# Power.net
KiCad netlist of a schematic drawn in Altium Designer
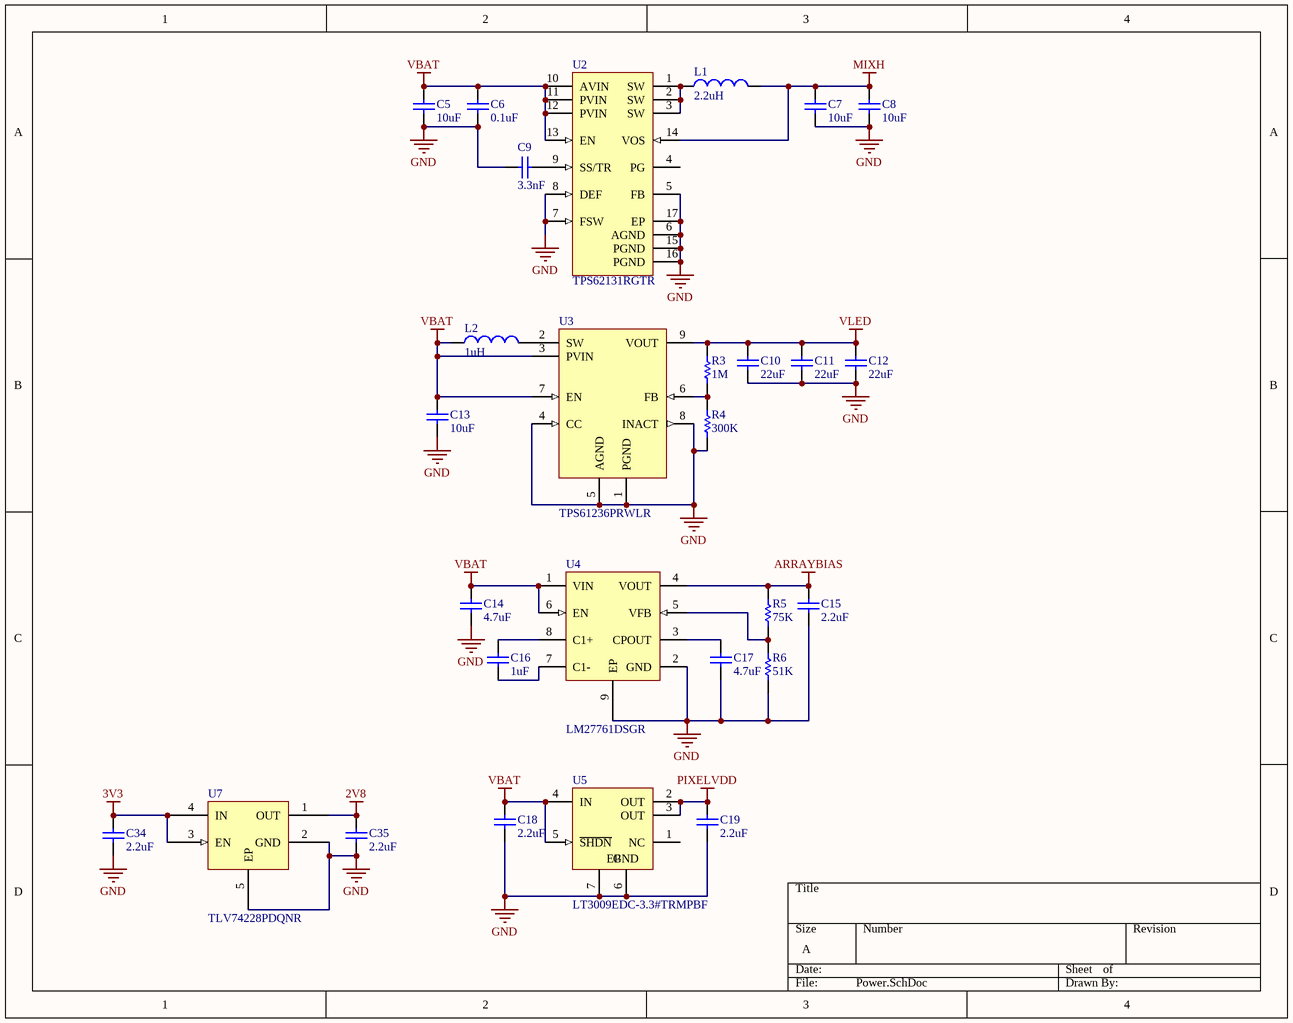
[diagram p0: Power.SchDoc]

(export (version "E")
  (design (tool "Eeschema 10.0.6"))
  (components
    (comp (ref "C5")
      (value "10uF")
      (footprint "C0402[1005X55]")
      (description "10uF 6.3V 20% 0402 (1005 Metric)")
      (fields (field (name "PARTNUMBER") "GRM155R60J106ME44D") (field (name "MANUFACTURER") "Murata"))
      (libsource (lib "Capacitors") (part "CAP_10uF_6.3V_0402_20%"))
    )
    (comp (ref "C6")
      (value "0.1uF")
      (footprint "C0201[0603X30]")
      (description "0.1uF 6.3V 10% 0201 (0603 Metric)")
      (fields (field (name "PARTNUMBER") "GRT033R60J104KE01D") (field (name "MANUFACTURER") "Murata"))
      (libsource (lib "Capacitors") (part "CAP_0.1uF_6.3V_0201_10%"))
    )
    (comp (ref "C7")
      (value "10uF")
      (footprint "C0402[1005X55]")
      (description "10uF 6.3V 20% 0402 (1005 Metric)")
      (fields (field (name "PARTNUMBER") "GRM155R60J106ME44D") (field (name "MANUFACTURER") "Murata"))
      (libsource (lib "Capacitors") (part "CAP_10uF_6.3V_0402_20%"))
    )
    (comp (ref "C8")
      (value "10uF")
      (footprint "C0402[1005X55]")
      (description "10uF 6.3V 20% 0402 (1005 Metric)")
      (fields (field (name "PARTNUMBER") "GRM155R60J106ME44D") (field (name "MANUFACTURER") "Murata"))
      (libsource (lib "Capacitors") (part "CAP_10uF_6.3V_0402_20%"))
    )
    (comp (ref "C9")
      (value "3.3nF")
      (footprint "C0201[0603X30]")
      (description "3.3nF 6.3V 10% 0201 (0603 Metric)")
      (fields (field (name "PARTNUMBER") "GRM033R70J332KA01D") (field (name "MANUFACTURER") "Murata"))
      (libsource (lib "Capacitors") (part "CAP_3,3nF_6.3V_0201_10%"))
    )
    (comp (ref "C10")
      (value "22uF")
      (footprint "C0603[1608X92]")
      (description "22uF 6.3V 10% 0603 (1608 Metric)")
      (fields (field (name "PARTNUMBER") "GRT188R60J226ME13D") (field (name "MANUFACTURER") "Murata"))
      (libsource (lib "Capacitors") (part "CAP_22uF_6.3V_0603_10%"))
    )
    (comp (ref "C11")
      (value "22uF")
      (footprint "C0603[1608X92]")
      (description "22uF 6.3V 10% 0603 (1608 Metric)")
      (fields (field (name "PARTNUMBER") "GRT188R60J226ME13D") (field (name "MANUFACTURER") "Murata"))
      (libsource (lib "Capacitors") (part "CAP_22uF_6.3V_0603_10%"))
    )
    (comp (ref "C12")
      (value "22uF")
      (footprint "C0603[1608X92]")
      (description "22uF 6.3V 10% 0603 (1608 Metric)")
      (fields (field (name "PARTNUMBER") "GRT188R60J226ME13D") (field (name "MANUFACTURER") "Murata"))
      (libsource (lib "Capacitors") (part "CAP_22uF_6.3V_0603_10%"))
    )
    (comp (ref "C13")
      (value "10uF")
      (footprint "C0402[1005X55]")
      (description "10uF 6.3V 20% 0402 (1005 Metric)")
      (fields (field (name "PARTNUMBER") "GRM155R60J106ME44D") (field (name "MANUFACTURER") "Murata"))
      (libsource (lib "Capacitors") (part "CAP_10uF_6.3V_0402_20%"))
    )
    (comp (ref "C14")
      (value "4.7uF")
      (footprint "C0402[1005X55]")
      (description "4.7uF 6.3V 20% 0402 (1005 Metric)")
      (fields (field (name "PARTNUMBER") "GRM155R60J475ME47D") (field (name "MANUFACTURER") "Murata"))
      (libsource (lib "Capacitors") (part "CAP_4.7uF_6.3V_0402_20%"))
    )
    (comp (ref "C15")
      (value "2.2uF")
      (footprint "C0402[1005X55]")
      (description "2.2uF 6.3V 20% 0402 (1005 Metric)")
      (fields (field (name "PARTNUMBER") "GRM155R60J225ME15D") (field (name "MANUFACTURER") "Murata"))
      (libsource (lib "Capacitors") (part "CAP_2.2uF_6.3V_0402_20%"))
    )
    (comp (ref "C16")
      (value "1uF")
      (footprint "C0402[1005X55]")
      (description "1uF 6.3V 10% 0402 (1005 Metric)")
      (fields (field (name "PARTNUMBER") "GRM155R70J105KA12D") (field (name "MANUFACTURER") "Murata"))
      (libsource (lib "Capacitors") (part "CAP_1uF_6.3V_0402_10%"))
    )
    (comp (ref "C17")
      (value "4.7uF")
      (footprint "C0402[1005X55]")
      (description "4.7uF 6.3V 20% 0402 (1005 Metric)")
      (fields (field (name "PARTNUMBER") "GRM155R60J475ME47D") (field (name "MANUFACTURER") "Murata"))
      (libsource (lib "Capacitors") (part "CAP_4.7uF_6.3V_0402_20%"))
    )
    (comp (ref "C18")
      (value "2.2uF")
      (footprint "C0402[1005X55]")
      (description "2.2uF 6.3V 20% 0402 (1005 Metric)")
      (fields (field (name "PARTNUMBER") "GRM155R60J225ME15D") (field (name "MANUFACTURER") "Murata"))
      (libsource (lib "Capacitors") (part "CAP_2.2uF_6.3V_0402_20%"))
    )
    (comp (ref "C19")
      (value "2.2uF")
      (footprint "C0402[1005X55]")
      (description "2.2uF 6.3V 20% 0402 (1005 Metric)")
      (fields (field (name "PARTNUMBER") "GRM155R60J225ME15D") (field (name "MANUFACTURER") "Murata"))
      (libsource (lib "Capacitors") (part "CAP_2.2uF_6.3V_0402_20%"))
    )
    (comp (ref "C34")
      (value "2.2uF")
      (footprint "C0402[1005X55]")
      (description "2.2uF 6.3V 20% 0402 (1005 Metric)")
      (fields (field (name "PARTNUMBER") "GRM155R60J225ME15D") (field (name "MANUFACTURER") "Murata"))
      (libsource (lib "Capacitors") (part "CAP_2.2uF_6.3V_0402_20%"))
    )
    (comp (ref "C35")
      (value "2.2uF")
      (footprint "C0402[1005X55]")
      (description "2.2uF 6.3V 20% 0402 (1005 Metric)")
      (fields (field (name "PARTNUMBER") "GRM155R60J225ME15D") (field (name "MANUFACTURER") "Murata"))
      (libsource (lib "Capacitors") (part "CAP_2.2uF_6.3V_0402_20%"))
    )
    (comp (ref "L1")
      (value "2.2uH")
      (footprint "IND1008")
      (description "2.2uH 20% 3.3A 1008")
      (fields (field (name "PARTNUMBER") "DFE252012F-2R2M=P2") (field (name "MANUFACTURER") "Murata"))
      (libsource (lib "Inductors") (part "IND_2.2uH_3.3A_1008_20%"))
    )
    (comp (ref "L2")
      (value "1uH")
      (footprint "IND1008")
      (description "1uH 20% 4.7A 1008")
      (fields (field (name "PARTNUMBER") "DFE252012F-2R2M=P2") (field (name "MANUFACTURER") "Murata"))
      (libsource (lib "Inductors") (part "IND_1uH_4.7A_1008_20%"))
    )
    (comp (ref "R3")
      (value "1M")
      (footprint "R0402[1005]")
      (description "1M 0.063W 1% 0402 (1005 Metric)")
      (fields (field (name "MANUFACTURER") "KOA Speer") (field (name "PARTNUMBER") "RK73H1ETTP1004F"))
      (libsource (lib "Resistors") (part "RES_1M_0402_1%"))
    )
    (comp (ref "R4")
      (value "300K")
      (footprint "R0402[1005]")
      (description "300K 0.063W 1% 0402 (1005 Metric)")
      (fields (field (name "MANUFACTURER") "KOA Speer") (field (name "PARTNUMBER") "RK73H1ETTP3003F"))
      (libsource (lib "Resistors") (part "RES_300K_0402_1%"))
    )
    (comp (ref "R5")
      (value "75K")
      (footprint "R0402[1005]")
      (description "75K 0.063W 1% 0402 (1005 Metric)")
      (fields (field (name "MANUFACTURER") "KOA Speer") (field (name "PARTNUMBER") "RK73H1ETTP7502F"))
      (libsource (lib "Resistors") (part "RES_75K_0402_1%"))
    )
    (comp (ref "R6")
      (value "51K")
      (footprint "R0402[1005]")
      (description "51K 0.063W 1% 0402 (1005 Metric)")
      (fields (field (name "MANUFACTURER") "KOA Speer") (field (name "PARTNUMBER") "RK73H1ETTP5102F"))
      (libsource (lib "Resistors") (part "RES_51K_0402_1%"))
    )
    (comp (ref "U2")
      (value "TPS62131RGTR")
      (footprint "RGT0016C_V")
      (fields (field (name "MANUFACTURER") "Texas Instruments"))
      (libsource (lib "Altium Content Vault") (part "TI-TPS62131RGT16-1700X1700TP"))
    )
    (comp (ref "U3")
      (value "TPS61236PRWLR")
      (footprint "VQFN-9")
      (fields (field (name "MANUFACTURER") "Texas Instruments"))
      (libsource (lib "ICs") (part "TPS61236PRWLR"))
    )
    (comp (ref "U4")
      (value "LM27761DSGR")
      (footprint "WSON-8")
      (description "Switching Voltage Regulators Switch Cap Boost")
      (fields (field (name "MANUFACTURER") "Texas Instruments"))
      (libsource (lib "ICs") (part "LM27761DSGR"))
    )
    (comp (ref "U5")
      (value "LT3009EDC-3.3#TRMPBF")
      (footprint "LT-DC6-6_V")
      (fields (field (name "MANUFACTURER") "Linear Technology"))
      (libsource (lib "Altium Content Vault") (part "LT-LT3009-DC6-6"))
    )
    (comp (ref "U7")
      (value "TLV74228PDQNR")
      (footprint "X2SON-4")
      (fields (field (name "MANUFACTURER") "Texas Instruments") (field (name "PARTNUMBER") "TLV74218PDQNR"))
      (libsource (lib "ICs") (part "TLV74228PDQNR"))
    )
  )
  (nets
    (net (code "1") (name "2V8") (class "Default")
      (node (ref "C35") (pin "2") (pinfunction "2_2") (pintype "passive"))
      (node (ref "U7") (pin "1") (pinfunction "OUT_1") (pintype "power_in"))
    )
    (net (code "2") (name "3V3") (class "Default")
      (node (ref "C34") (pin "2") (pinfunction "2_2") (pintype "passive"))
      (node (ref "U7") (pin "3") (pinfunction "EN_3") (pintype "input"))
      (node (ref "U7") (pin "4") (pinfunction "IN_4") (pintype "power_in"))
    )
    (net (code "3") (name "ARRAYBIAS") (class "Default")
      (node (ref "C15") (pin "2") (pinfunction "2_2") (pintype "passive"))
      (node (ref "R5") (pin "2") (pinfunction "2_2") (pintype "passive"))
      (node (ref "U4") (pin "4") (pinfunction "VOUT_4") (pintype "power_in"))
    )
    (net (code "4") (name "GND") (class "Default")
      (node (ref "C10") (pin "1") (pinfunction "1_1") (pintype "passive"))
      (node (ref "C11") (pin "1") (pinfunction "1_1") (pintype "passive"))
      (node (ref "C12") (pin "1") (pinfunction "1_1") (pintype "passive"))
      (node (ref "C13") (pin "1") (pinfunction "1_1") (pintype "passive"))
      (node (ref "C14") (pin "1") (pinfunction "1_1") (pintype "passive"))
      (node (ref "C15") (pin "1") (pinfunction "1_1") (pintype "passive"))
      (node (ref "C17") (pin "1") (pinfunction "1_1") (pintype "passive"))
      (node (ref "C18") (pin "1") (pinfunction "1_1") (pintype "passive"))
      (node (ref "C19") (pin "1") (pinfunction "1_1") (pintype "passive"))
      (node (ref "C34") (pin "1") (pinfunction "1_1") (pintype "passive"))
      (node (ref "C35") (pin "1") (pinfunction "1_1") (pintype "passive"))
      (node (ref "C5") (pin "1") (pinfunction "1_1") (pintype "passive"))
      (node (ref "C6") (pin "1") (pinfunction "1_1") (pintype "passive"))
      (node (ref "C7") (pin "1") (pinfunction "1_1") (pintype "passive"))
      (node (ref "C8") (pin "1") (pinfunction "1_1") (pintype "passive"))
      (node (ref "C9") (pin "1") (pinfunction "1_1") (pintype "passive"))
      (node (ref "R4") (pin "1") (pinfunction "1_1") (pintype "passive"))
      (node (ref "R6") (pin "1") (pinfunction "1_1") (pintype "passive"))
      (node (ref "U2") (pin "15") (pinfunction "PGND_15") (pintype "power_in"))
      (node (ref "U2") (pin "16") (pinfunction "PGND_16") (pintype "power_in"))
      (node (ref "U2") (pin "17") (pinfunction "EP_17") (pintype "power_in"))
      (node (ref "U2") (pin "5") (pinfunction "FB_5") (pintype "passive"))
      (node (ref "U2") (pin "6") (pinfunction "AGND_6") (pintype "power_in"))
      (node (ref "U2") (pin "7") (pinfunction "FSW_7") (pintype "input"))
      (node (ref "U2") (pin "8") (pinfunction "DEF_8") (pintype "input"))
      (node (ref "U3") (pin "1") (pinfunction "PGND_1") (pintype "power_in"))
      (node (ref "U3") (pin "4") (pinfunction "CC_4") (pintype "input"))
      (node (ref "U3") (pin "5") (pinfunction "AGND_5") (pintype "power_in"))
      (node (ref "U3") (pin "8") (pinfunction "INACT_8") (pintype "output"))
      (node (ref "U4") (pin "2") (pinfunction "GND_2") (pintype "power_in"))
      (node (ref "U4") (pin "9") (pinfunction "EP_9") (pintype "passive"))
      (node (ref "U5") (pin "6") (pinfunction "GND_6") (pintype "power_in"))
      (node (ref "U5") (pin "7") (pinfunction "EP_7") (pintype "power_in"))
      (node (ref "U7") (pin "2") (pinfunction "GND_2") (pintype "power_in"))
      (node (ref "U7") (pin "5") (pinfunction "EP_5") (pintype "power_in"))
    )
    (net (code "5") (name "MIXH") (class "Default")
      (node (ref "C7") (pin "2") (pinfunction "2_2") (pintype "passive"))
      (node (ref "C8") (pin "2") (pinfunction "2_2") (pintype "passive"))
      (node (ref "L1") (pin "2") (pinfunction "2_2") (pintype "passive"))
      (node (ref "U2") (pin "14") (pinfunction "VOS_14") (pintype "input"))
    )
    (net (code "6") (name "Net-(L1-Pad1)") (class "Default")
      (node (ref "L1") (pin "1") (pinfunction "1_1") (pintype "passive"))
      (node (ref "U2") (pin "1") (pinfunction "SW_1") (pintype "power_in"))
      (node (ref "U2") (pin "2") (pinfunction "SW_2") (pintype "power_in"))
      (node (ref "U2") (pin "3") (pinfunction "SW_3") (pintype "power_in"))
    )
    (net (code "7") (name "Net-(U2-SS{slash}TR)") (class "Default")
      (node (ref "C9") (pin "2") (pinfunction "2_2") (pintype "passive"))
      (node (ref "U2") (pin "9") (pinfunction "SS/TR_9") (pintype "input"))
    )
    (net (code "8") (name "Net-(U3-FB)") (class "Default")
      (node (ref "R3") (pin "1") (pinfunction "1_1") (pintype "passive"))
      (node (ref "R4") (pin "2") (pinfunction "2_2") (pintype "passive"))
      (node (ref "U3") (pin "6") (pinfunction "FB_6") (pintype "input"))
    )
    (net (code "9") (name "Net-(U3-SW)") (class "Default")
      (node (ref "L2") (pin "2") (pinfunction "2_2") (pintype "passive"))
      (node (ref "U3") (pin "2") (pinfunction "SW_2") (pintype "power_in"))
    )
    (net (code "10") (name "Net-(U4-C1+)") (class "Default")
      (node (ref "C16") (pin "2") (pinfunction "2_2") (pintype "passive"))
      (node (ref "U4") (pin "8") (pinfunction "C1+_8") (pintype "power_in"))
    )
    (net (code "11") (name "Net-(U4-C1-)") (class "Default")
      (node (ref "C16") (pin "1") (pinfunction "1_1") (pintype "passive"))
      (node (ref "U4") (pin "7") (pinfunction "C1-_7") (pintype "power_in"))
    )
    (net (code "12") (name "Net-(U4-CPOUT)") (class "Default")
      (node (ref "C17") (pin "2") (pinfunction "2_2") (pintype "passive"))
      (node (ref "U4") (pin "3") (pinfunction "CPOUT_3") (pintype "power_in"))
    )
    (net (code "13") (name "Net-(U4-VFB)") (class "Default")
      (node (ref "R5") (pin "1") (pinfunction "1_1") (pintype "passive"))
      (node (ref "R6") (pin "2") (pinfunction "2_2") (pintype "passive"))
      (node (ref "U4") (pin "5") (pinfunction "VFB_5") (pintype "input"))
    )
    (net (code "14") (name "PIXELVDD") (class "Default")
      (node (ref "C19") (pin "2") (pinfunction "2_2") (pintype "passive"))
      (node (ref "U5") (pin "2") (pinfunction "OUT_2") (pintype "power_in"))
      (node (ref "U5") (pin "3") (pinfunction "OUT_3") (pintype "power_in"))
    )
    (net (code "15") (name "VBAT") (class "Default")
      (node (ref "C13") (pin "2") (pinfunction "2_2") (pintype "passive"))
      (node (ref "C14") (pin "2") (pinfunction "2_2") (pintype "passive"))
      (node (ref "C18") (pin "2") (pinfunction "2_2") (pintype "passive"))
      (node (ref "C5") (pin "2") (pinfunction "2_2") (pintype "passive"))
      (node (ref "C6") (pin "2") (pinfunction "2_2") (pintype "passive"))
      (node (ref "L2") (pin "1") (pinfunction "1_1") (pintype "passive"))
      (node (ref "U2") (pin "10") (pinfunction "AVIN_10") (pintype "power_in"))
      (node (ref "U2") (pin "11") (pinfunction "PVIN_11") (pintype "power_in"))
      (node (ref "U2") (pin "12") (pinfunction "PVIN_12") (pintype "power_in"))
      (node (ref "U2") (pin "13") (pinfunction "EN_13") (pintype "input"))
      (node (ref "U3") (pin "3") (pinfunction "PVIN_3") (pintype "power_in"))
      (node (ref "U3") (pin "7") (pinfunction "EN_7") (pintype "input"))
      (node (ref "U4") (pin "1") (pinfunction "VIN_1") (pintype "power_in"))
      (node (ref "U4") (pin "6") (pinfunction "EN_6") (pintype "input"))
      (node (ref "U5") (pin "4") (pinfunction "IN_4") (pintype "power_in"))
      (node (ref "U5") (pin "5") (pinfunction "~{SHDN}_5") (pintype "input"))
    )
    (net (code "16") (name "VLED") (class "Default")
      (node (ref "C10") (pin "2") (pinfunction "2_2") (pintype "passive"))
      (node (ref "C11") (pin "2") (pinfunction "2_2") (pintype "passive"))
      (node (ref "C12") (pin "2") (pinfunction "2_2") (pintype "passive"))
      (node (ref "R3") (pin "2") (pinfunction "2_2") (pintype "passive"))
      (node (ref "U3") (pin "9") (pinfunction "VOUT_9") (pintype "power_in"))
    )
    (net (code "17") (name "unconnected-(U2-PG-Pad4)") (class "Default")
      (node (ref "U2") (pin "4") (pinfunction "PG_4") (pintype "tri_state"))
    )
    (net (code "18") (name "unconnected-(U5-NC-Pad1)") (class "Default")
      (node (ref "U5") (pin "1") (pinfunction "NC_1") (pintype "passive"))
    )
  )
)
